# PM-1_PDB.net
KiCad netlist of a schematic drawn in Altium Designer
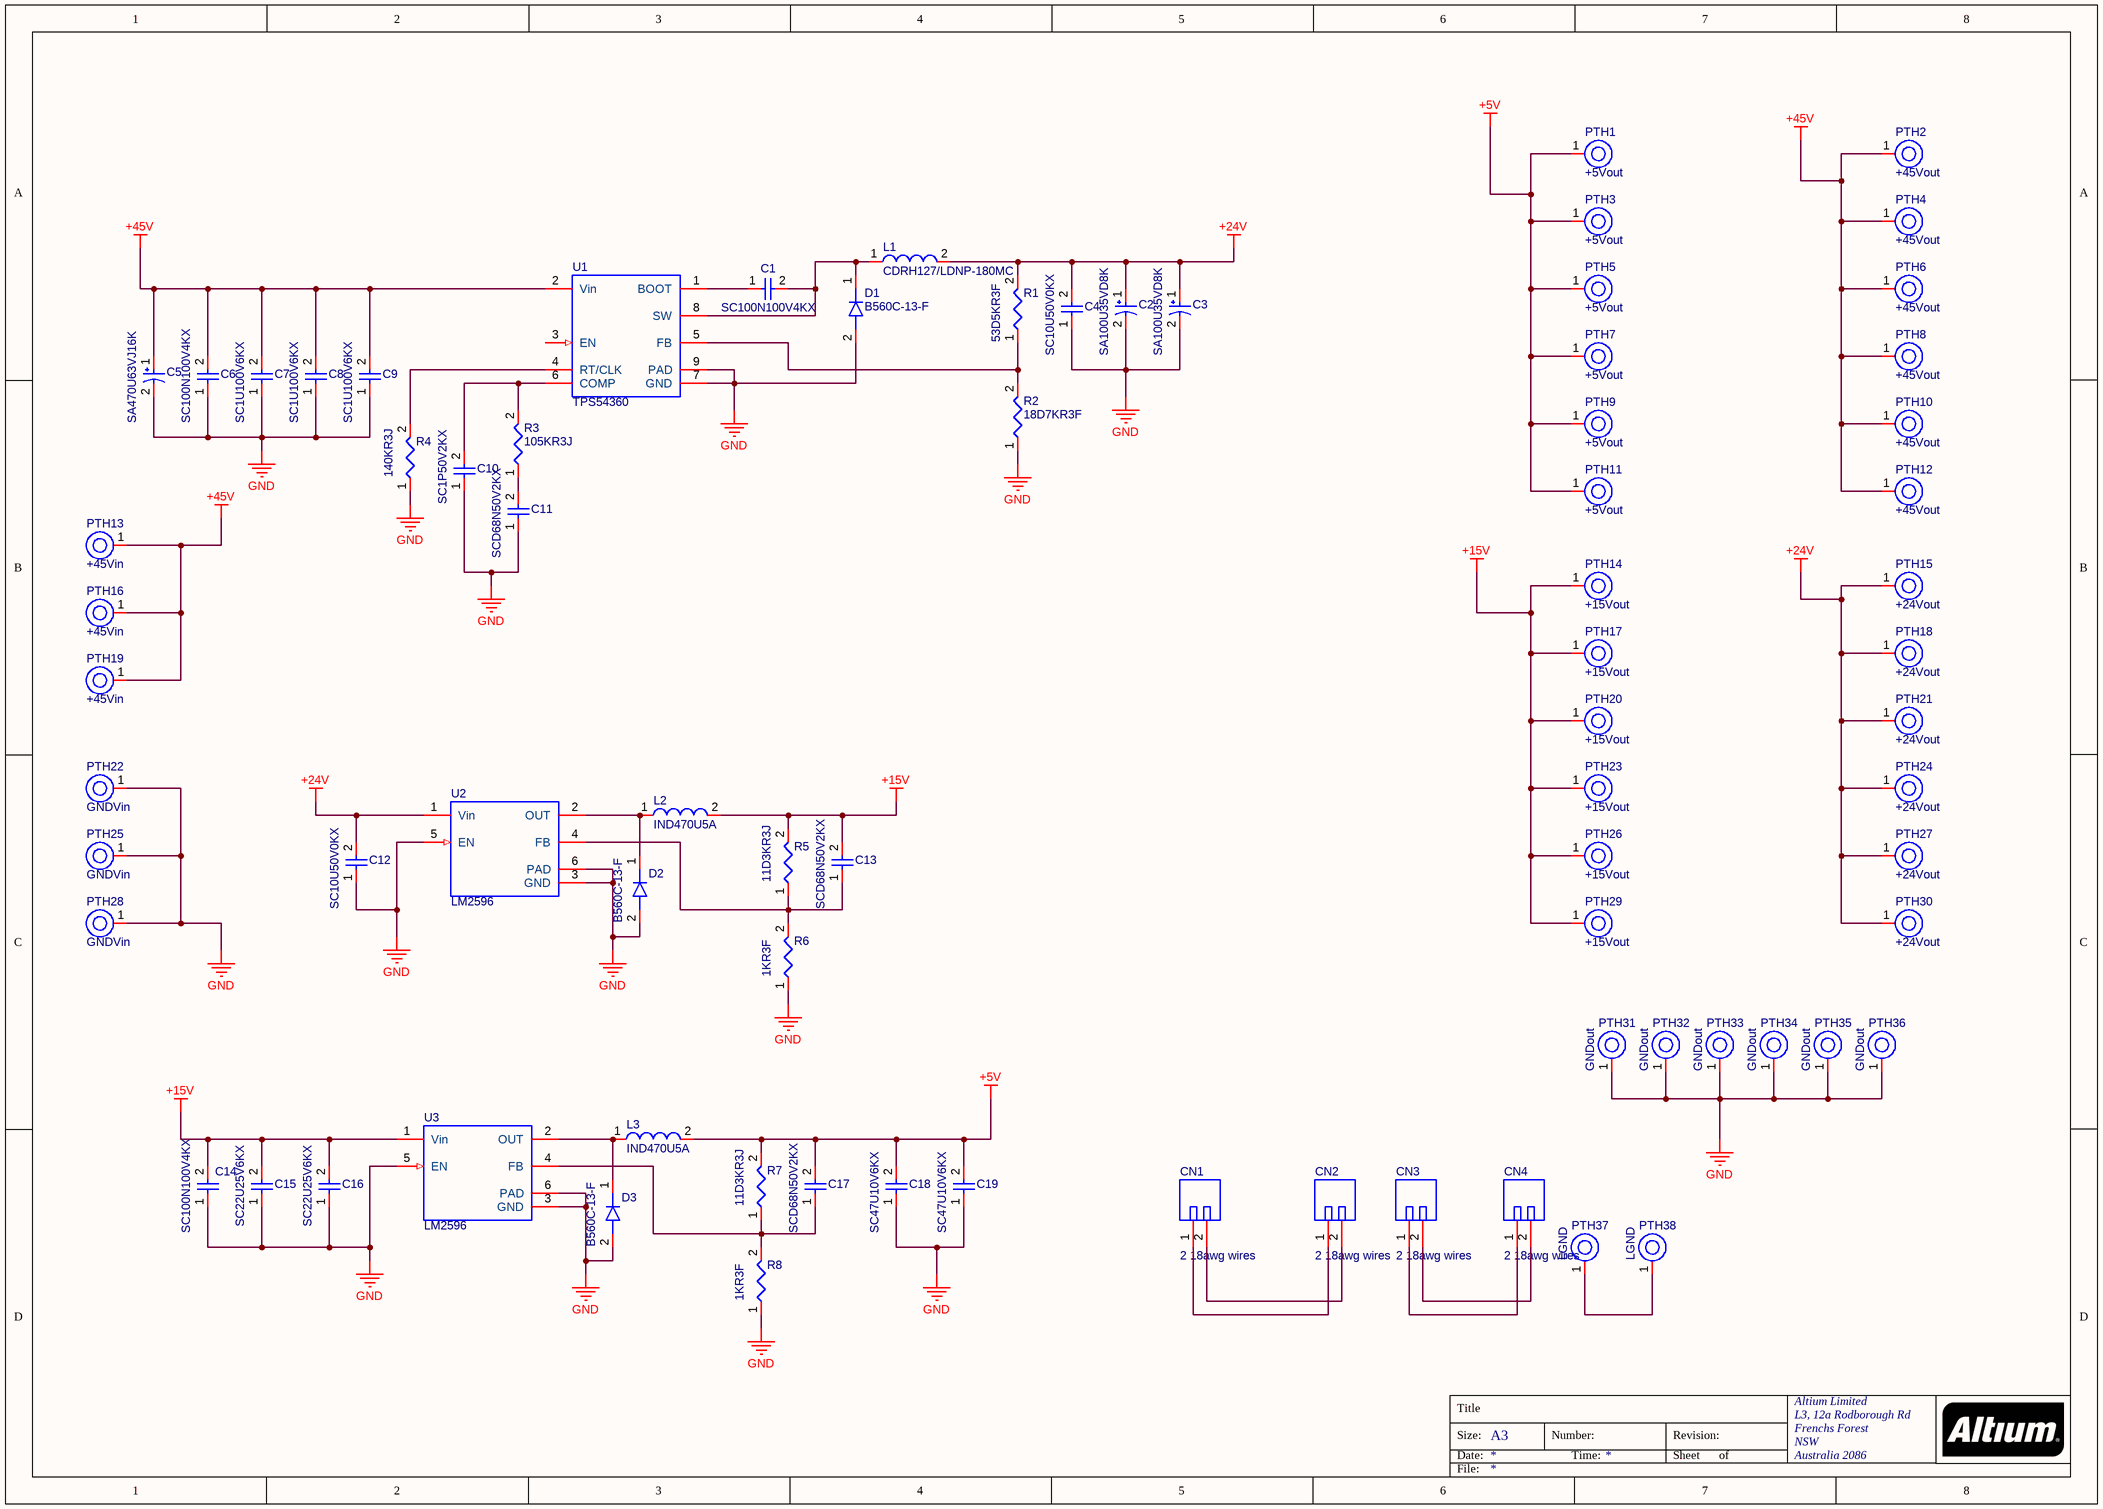
[diagram p0: PM-1_PDB.SchDoc]

(export (version "E")
  (design (tool "Eeschema 10.0.6"))
  (components
    (comp (ref "C1")
      (value "SC100N100V4KX")
      (footprint "CAPC0402(1005)60_L")
      (description "CAP 100nF 100V ±10% 0805(1610 Metric) Thickness 1mm SMD")
      (libsource (lib "PDB") (part "CAP(0805)100nF100V"))
    )
    (comp (ref "C2")
      (value "SA100U35VD8K")
      (footprint "CAPAE(D8)7666X80L")
      (description "CAP 100uF 35V ±10% D8 Thickness 7.7mm SMD")
      (libsource (lib "PDB") (part "CAP(D8)100UF35V"))
    )
    (comp (ref "C3")
      (value "SA100U35VD8K")
      (footprint "CAPAE(D8)7666X80L")
      (description "CAP 100uF 35V ±10% D8 Thickness 7.7mm SMD")
      (libsource (lib "PDB") (part "CAP(D8)100UF35V"))
    )
    (comp (ref "C4")
      (value "SC10U50V0KX")
      (footprint "CAPC3225X27L")
      (description "CAP 10uF 50V ±10% 1210(3225 Metric) Thickness 1.7mm SMD")
      (libsource (lib "PDB") (part "CAP(1210)10UF50V"))
    )
    (comp (ref "C5")
      (value "SA470U63VJ16K")
      (footprint "CAPAE184170X170L")
      (description "EEVFK1J471M CAP 470uF 63V ±10% J16 Thickness 17mm SMD")
      (libsource (lib "PDB") (part "CAP(J16)470UF63V"))
    )
    (comp (ref "C6")
      (value "SC100N100V4KX")
      (footprint "CAPC0402(1005)60_L")
      (description "CAP 100nF 100V ±10% 0805(1610 Metric) Thickness 1mm SMD")
      (libsource (lib "PDB") (part "CAP(0805)100nF100V"))
    )
    (comp (ref "C7")
      (value "SC1U100V6KX")
      (footprint "CAPC1206(3216)")
      (description "CAP 1uF 100V ±10% 1206(3216 Metric) Thickness 1.8mm SMD")
      (libsource (lib "PDB") (part "CAP(1206)1UF100V"))
    )
    (comp (ref "C8")
      (value "SC1U100V6KX")
      (footprint "CAPC1206(3216)")
      (description "CAP 1uF 100V ±10% 1206(3216 Metric) Thickness 1.8mm SMD")
      (libsource (lib "PDB") (part "CAP(1206)1UF100V"))
    )
    (comp (ref "C9")
      (value "SC1U100V6KX")
      (footprint "CAPC1206(3216)")
      (description "CAP 1uF 100V ±10% 1206(3216 Metric) Thickness 1.8mm SMD")
      (libsource (lib "PDB") (part "CAP(1206)1UF100V"))
    )
    (comp (ref "C10")
      (value "SC1P50V2KX")
      (footprint "CAPC0402(1005)60_L")
      (description "CAP 1pF 50V ±10% 0402 (1005 Metric) Thickness 0.6mm SMD")
      (libsource (lib "PDB") (part "CAP(0402)1pF50V"))
    )
    (comp (ref "C11")
      (value "SCD68N50V2KX")
      (footprint "CAPC0402(1005)60_L")
      (description "CAP 680pF 50V ±10% 0402 (1005 Metric) Thickness 0.6mm SMD")
      (libsource (lib "PDB") (part "CAP(0402)680pF50V"))
    )
    (comp (ref "C12")
      (value "SC10U50V0KX")
      (footprint "CAPC3225X27L")
      (description "CAP 10uF 50V ±10% 1210(3225 Metric) Thickness 1.7mm SMD")
      (libsource (lib "PDB") (part "CAP(1210)10UF50V"))
    )
    (comp (ref "C13")
      (value "SCD68N50V2KX")
      (footprint "CAPC0402(1005)60_L")
      (description "CAP 680pF 50V ±10% 0402 (1005 Metric) Thickness 0.6mm SMD")
      (libsource (lib "PDB") (part "CAP(0402)680pF50V"))
    )
    (comp (ref "C14")
      (value "SC100N100V4KX")
      (footprint "CAPC0402(1005)60_L")
      (description "CAP 100nF 100V ±10% 0805(1610 Metric) Thickness 1mm SMD")
      (libsource (lib "PDB") (part "CAP(0805)100nF100V"))
    )
    (comp (ref "C15")
      (value "SC22U25V6KX")
      (footprint "CAPC1206(3216)")
      (description "CAP 22uF 25V ±10% 1206(3216 Metric) Thickness 1.8mm SMD")
      (libsource (lib "PDB") (part "CAP(1206)22UF25V"))
    )
    (comp (ref "C16")
      (value "SC22U25V6KX")
      (footprint "CAPC1206(3216)")
      (description "CAP 22uF 25V ±10% 1206(3216 Metric) Thickness 1.8mm SMD")
      (libsource (lib "PDB") (part "CAP(1206)22UF25V"))
    )
    (comp (ref "C17")
      (value "SCD68N50V2KX")
      (footprint "CAPC0402(1005)60_L")
      (description "CAP 680pF 50V ±10% 0402 (1005 Metric) Thickness 0.6mm SMD")
      (libsource (lib "PDB") (part "CAP(0402)680pF50V"))
    )
    (comp (ref "C18")
      (value "SC47U10V6KX")
      (footprint "CAPC1206(3216)")
      (description "CAP 47uF 10V ±10% 1206(3216 Metric) Thickness 1.8mm SMD")
      (libsource (lib "PDB") (part "CAP(1206)47UF10V"))
    )
    (comp (ref "C19")
      (value "SC47U10V6KX")
      (footprint "CAPC1206(3216)")
      (description "CAP 47uF 10V ±10% 1206(3216 Metric) Thickness 1.8mm SMD")
      (libsource (lib "PDB") (part "CAP(1206)47UF10V"))
    )
    (comp (ref "CN1")
      (value "2 18awg wires")
      (footprint "2PHEADERS-2D54")
      (description "2 holes for 18awg wire")
      (fields (field (name "MANUFACTURER") "JST"))
      (libsource (lib "PDB") (part "2PIN-CN"))
    )
    (comp (ref "CN2")
      (value "2 18awg wires")
      (footprint "2PHEADERS-2D54")
      (description "2 holes for 18awg wire")
      (fields (field (name "MANUFACTURER") "JST"))
      (libsource (lib "PDB") (part "2PIN-CN"))
    )
    (comp (ref "CN3")
      (value "2 18awg wires")
      (footprint "2PHEADERS-2D54")
      (description "2 holes for 18awg wire")
      (fields (field (name "MANUFACTURER") "JST"))
      (libsource (lib "PDB") (part "2PIN-CN"))
    )
    (comp (ref "CN4")
      (value "2 18awg wires")
      (footprint "2PHEADERS-2D54")
      (description "2 holes for 18awg wire")
      (fields (field (name "MANUFACTURER") "JST"))
      (libsource (lib "PDB") (part "2PIN-CN"))
    )
    (comp (ref "D1")
      (value "B560C-13-F")
      (footprint "SMC")
      (description "5.0A SURFACE MOUNT SCHOTTKY BARRIER RECTIFIER")
      (fields (field (name "MANUFACTURER") "Rohm"))
      (libsource (lib "PDB") (part "DIOD-B560C"))
    )
    (comp (ref "D2")
      (value "B560C-13-F")
      (footprint "SMC")
      (description "5.0A SURFACE MOUNT SCHOTTKY BARRIER RECTIFIER")
      (fields (field (name "MANUFACTURER") "Rohm"))
      (libsource (lib "PDB") (part "DIOD-B560C"))
    )
    (comp (ref "D3")
      (value "B560C-13-F")
      (footprint "SMC")
      (description "5.0A SURFACE MOUNT SCHOTTKY BARRIER RECTIFIER")
      (fields (field (name "MANUFACTURER") "Rohm"))
      (libsource (lib "PDB") (part "DIOD-B560C"))
    )
    (comp (ref "L1")
      (value "CDRH127/LDNP-180MC")
      (footprint "INDP120120X80L")
      (description "Inductor: SMD, 18 uHn, 5.1 A")
      (libsource (lib "PDB") (part "CDRH127"))
    )
    (comp (ref "L2")
      (value "IND470U5A")
      (footprint "INDP120120X80L")
      (description "Inductor: SMD, 47 uHn, 5 A")
      (libsource (lib "PDB") (part "IND470U5A"))
    )
    (comp (ref "L3")
      (value "IND470U5A")
      (footprint "INDP120120X80L")
      (description "Inductor: SMD, 47 uHn, 5 A")
      (libsource (lib "PDB") (part "IND470U5A"))
    )
    (comp (ref "PTH1")
      (value "+5Vout")
      (footprint "POWERHOLE-LP")
      (description "1.2mm hole 2mm pad")
      (libsource (lib "PUMAlib") (part "PTH-1D2M"))
    )
    (comp (ref "PTH2")
      (value "+45Vout")
      (footprint "POWERHOLE")
      (description "2mm hole 3.5mm pad")
      (libsource (lib "PUMAlib") (part "PTH-2M"))
    )
    (comp (ref "PTH3")
      (value "+5Vout")
      (footprint "POWERHOLE-LP")
      (description "1.2mm hole 2mm pad")
      (libsource (lib "PUMAlib") (part "PTH-1D2M"))
    )
    (comp (ref "PTH4")
      (value "+45Vout")
      (footprint "POWERHOLE")
      (description "2mm hole 3.5mm pad")
      (libsource (lib "PUMAlib") (part "PTH-2M"))
    )
    (comp (ref "PTH5")
      (value "+5Vout")
      (footprint "POWERHOLE-LP")
      (description "1.2mm hole 2mm pad")
      (libsource (lib "PUMAlib") (part "PTH-1D2M"))
    )
    (comp (ref "PTH6")
      (value "+45Vout")
      (footprint "POWERHOLE")
      (description "2mm hole 3.5mm pad")
      (libsource (lib "PUMAlib") (part "PTH-2M"))
    )
    (comp (ref "PTH7")
      (value "+5Vout")
      (footprint "POWERHOLE-LP")
      (description "1.2mm hole 2mm pad")
      (libsource (lib "PUMAlib") (part "PTH-1D2M"))
    )
    (comp (ref "PTH8")
      (value "+45Vout")
      (footprint "POWERHOLE")
      (description "2mm hole 3.5mm pad")
      (libsource (lib "PUMAlib") (part "PTH-2M"))
    )
    (comp (ref "PTH9")
      (value "+5Vout")
      (footprint "POWERHOLE-LP")
      (description "1.2mm hole 2mm pad")
      (libsource (lib "PUMAlib") (part "PTH-1D2M"))
    )
    (comp (ref "PTH10")
      (value "+45Vout")
      (footprint "POWERHOLE")
      (description "2mm hole 3.5mm pad")
      (libsource (lib "PUMAlib") (part "PTH-2M"))
    )
    (comp (ref "PTH11")
      (value "+5Vout")
      (footprint "POWERHOLE-LP")
      (description "1.2mm hole 2mm pad")
      (libsource (lib "PUMAlib") (part "PTH-1D2M"))
    )
    (comp (ref "PTH12")
      (value "+45Vout")
      (footprint "POWERHOLE")
      (description "2mm hole 3.5mm pad")
      (libsource (lib "PUMAlib") (part "PTH-2M"))
    )
    (comp (ref "PTH13")
      (value "+45Vin")
      (footprint "POWERHOLE")
      (description "2mm hole 3.5mm pad")
      (libsource (lib "PUMAlib") (part "PTH-2M"))
    )
    (comp (ref "PTH14")
      (value "+15Vout")
      (footprint "POWERHOLE-LP")
      (description "1.2mm hole 2mm pad")
      (libsource (lib "PUMAlib") (part "PTH-1D2M"))
    )
    (comp (ref "PTH15")
      (value "+24Vout")
      (footprint "POWERHOLE")
      (description "2mm hole 3.5mm pad")
      (libsource (lib "PUMAlib") (part "PTH-2M"))
    )
    (comp (ref "PTH16")
      (value "+45Vin")
      (footprint "POWERHOLE")
      (description "2mm hole 3.5mm pad")
      (libsource (lib "PUMAlib") (part "PTH-2M"))
    )
    (comp (ref "PTH17")
      (value "+15Vout")
      (footprint "POWERHOLE-LP")
      (description "1.2mm hole 2mm pad")
      (libsource (lib "PUMAlib") (part "PTH-1D2M"))
    )
    (comp (ref "PTH18")
      (value "+24Vout")
      (footprint "POWERHOLE")
      (description "2mm hole 3.5mm pad")
      (libsource (lib "PUMAlib") (part "PTH-2M"))
    )
    (comp (ref "PTH19")
      (value "+45Vin")
      (footprint "POWERHOLE")
      (description "2mm hole 3.5mm pad")
      (libsource (lib "PUMAlib") (part "PTH-2M"))
    )
    (comp (ref "PTH20")
      (value "+15Vout")
      (footprint "POWERHOLE-LP")
      (description "1.2mm hole 2mm pad")
      (libsource (lib "PUMAlib") (part "PTH-1D2M"))
    )
    (comp (ref "PTH21")
      (value "+24Vout")
      (footprint "POWERHOLE")
      (description "2mm hole 3.5mm pad")
      (libsource (lib "PUMAlib") (part "PTH-2M"))
    )
    (comp (ref "PTH22")
      (value "GNDVin")
      (footprint "POWERHOLE")
      (description "2mm hole 3.5mm pad")
      (libsource (lib "PUMAlib") (part "PTH-2M"))
    )
    (comp (ref "PTH23")
      (value "+15Vout")
      (footprint "POWERHOLE-LP")
      (description "1.2mm hole 2mm pad")
      (libsource (lib "PUMAlib") (part "PTH-1D2M"))
    )
    (comp (ref "PTH24")
      (value "+24Vout")
      (footprint "POWERHOLE")
      (description "2mm hole 3.5mm pad")
      (libsource (lib "PUMAlib") (part "PTH-2M"))
    )
    (comp (ref "PTH25")
      (value "GNDVin")
      (footprint "POWERHOLE")
      (description "2mm hole 3.5mm pad")
      (libsource (lib "PUMAlib") (part "PTH-2M"))
    )
    (comp (ref "PTH26")
      (value "+15Vout")
      (footprint "POWERHOLE-LP")
      (description "1.2mm hole 2mm pad")
      (libsource (lib "PUMAlib") (part "PTH-1D2M"))
    )
    (comp (ref "PTH27")
      (value "+24Vout")
      (footprint "POWERHOLE")
      (description "2mm hole 3.5mm pad")
      (libsource (lib "PUMAlib") (part "PTH-2M"))
    )
    (comp (ref "PTH28")
      (value "GNDVin")
      (footprint "POWERHOLE")
      (description "2mm hole 3.5mm pad")
      (libsource (lib "PUMAlib") (part "PTH-2M"))
    )
    (comp (ref "PTH29")
      (value "+15Vout")
      (footprint "POWERHOLE-LP")
      (description "1.2mm hole 2mm pad")
      (libsource (lib "PUMAlib") (part "PTH-1D2M"))
    )
    (comp (ref "PTH30")
      (value "+24Vout")
      (footprint "POWERHOLE")
      (description "2mm hole 3.5mm pad")
      (libsource (lib "PUMAlib") (part "PTH-2M"))
    )
    (comp (ref "PTH31")
      (value "GNDout")
      (footprint "POWERHOLE")
      (description "2mm hole 3.5mm pad")
      (libsource (lib "PUMAlib") (part "PTH-2M"))
    )
    (comp (ref "PTH32")
      (value "GNDout")
      (footprint "POWERHOLE")
      (description "2mm hole 3.5mm pad")
      (libsource (lib "PUMAlib") (part "PTH-2M"))
    )
    (comp (ref "PTH33")
      (value "GNDout")
      (footprint "POWERHOLE")
      (description "2mm hole 3.5mm pad")
      (libsource (lib "PUMAlib") (part "PTH-2M"))
    )
    (comp (ref "PTH34")
      (value "GNDout")
      (footprint "POWERHOLE")
      (description "2mm hole 3.5mm pad")
      (libsource (lib "PUMAlib") (part "PTH-2M"))
    )
    (comp (ref "PTH35")
      (value "GNDout")
      (footprint "POWERHOLE")
      (description "2mm hole 3.5mm pad")
      (libsource (lib "PUMAlib") (part "PTH-2M"))
    )
    (comp (ref "PTH36")
      (value "GNDout")
      (footprint "POWERHOLE")
      (description "2mm hole 3.5mm pad")
      (libsource (lib "PUMAlib") (part "PTH-2M"))
    )
    (comp (ref "PTH37")
      (value "LGND")
      (footprint "POWERHOLE-LP")
      (description "1.2mm hole 2mm pad")
      (libsource (lib "PUMAlib") (part "PTH-1D2M"))
    )
    (comp (ref "PTH38")
      (value "LGND")
      (footprint "POWERHOLE-LP")
      (description "1.2mm hole 2mm pad")
      (libsource (lib "PUMAlib") (part "PTH-1D2M"))
    )
    (comp (ref "R1")
      (value "53D5KR3F")
      (footprint "RESC0603(1608)_L")
      (description "53.5K 0.1W 1% 0603 (1608 Metric)  SMD")
      (libsource (lib "PDB") (part "RES0(0603)_53D5K"))
    )
    (comp (ref "R2")
      (value "18D7KR3F")
      (footprint "RESC0603(1608)_L")
      (description "18.7K 0.1W 1% 0603 (1608 Metric)  SMD")
      (libsource (lib "PDB") (part "RES0(0603)_1D8K"))
    )
    (comp (ref "R3")
      (value "105KR3J")
      (footprint "RESC0603(1608)_L")
      (description "105K 0.1W 5% 0603 (1608 Metric)  SMD")
      (libsource (lib "PDB") (part "RES0(0603)_105K"))
    )
    (comp (ref "R4")
      (value "140KR3J")
      (footprint "RESC0603(1608)_L")
      (description "140K 0.1W 5% 0603 (1608 Metric)  SMD")
      (libsource (lib "PDB") (part "RES0(0603)_140K"))
    )
    (comp (ref "R5")
      (value "11D3KR3J")
      (footprint "RESC0603(1608)_L")
      (description "11.3K 0.1W 5% 0603 (1608 Metric)  SMD")
      (libsource (lib "PDB") (part "RES0(0603)_11D3K"))
    )
    (comp (ref "R6")
      (value "1KR3F")
      (footprint "RESC0603(1608)_L")
      (description "1K 0.1W 1% 0603 (1608 Metric)  SMD")
      (libsource (lib "PDB") (part "RES0(0603)_1K"))
    )
    (comp (ref "R7")
      (value "11D3KR3J")
      (footprint "RESC0603(1608)_L")
      (description "11.3K 0.1W 5% 0603 (1608 Metric)  SMD")
      (libsource (lib "PDB") (part "RES0(0603)_11D3K"))
    )
    (comp (ref "R8")
      (value "1KR3F")
      (footprint "RESC0603(1608)_L")
      (description "1K 0.1W 1% 0603 (1608 Metric)  SMD")
      (libsource (lib "PDB") (part "RES0(0603)_1K"))
    )
    (comp (ref "U1")
      (value "TPS54360")
      (footprint "POWERSO8")
      (description "60 V Input, 3.5 A, Step Down DC-DC Converter")
      (libsource (lib "PDB") (part "TPS54360"))
    )
    (comp (ref "U2")
      (value "LM2596")
      (footprint "D2PAK")
      (description "4 V Input, 3 A, Step Down DC-DC Converter")
      (libsource (lib "PDB") (part "LM2596"))
    )
    (comp (ref "U3")
      (value "LM2596")
      (footprint "D2PAK")
      (description "4 V Input, 3 A, Step Down DC-DC Converter")
      (libsource (lib "PDB") (part "LM2596"))
    )
  )
  (nets
    (net (code "1") (name "+5V") (class "Default")
      (node (ref "C17") (pin "2") (pinfunction "2_2") (pintype "passive"))
      (node (ref "C18") (pin "2") (pinfunction "2_2") (pintype "passive"))
      (node (ref "C19") (pin "2") (pinfunction "2_2") (pintype "passive"))
      (node (ref "L3") (pin "2") (pinfunction "2_2") (pintype "passive"))
      (node (ref "PTH1") (pin "1") (pinfunction "H1_1") (pintype "passive"))
      (node (ref "PTH11") (pin "1") (pinfunction "H1_1") (pintype "passive"))
      (node (ref "PTH3") (pin "1") (pinfunction "H1_1") (pintype "passive"))
      (node (ref "PTH5") (pin "1") (pinfunction "H1_1") (pintype "passive"))
      (node (ref "PTH7") (pin "1") (pinfunction "H1_1") (pintype "passive"))
      (node (ref "PTH9") (pin "1") (pinfunction "H1_1") (pintype "passive"))
      (node (ref "R7") (pin "2") (pinfunction "2_2") (pintype "passive"))
    )
    (net (code "2") (name "+15V") (class "Default")
      (node (ref "C13") (pin "2") (pinfunction "2_2") (pintype "passive"))
      (node (ref "C14") (pin "2") (pinfunction "2_2") (pintype "passive"))
      (node (ref "C15") (pin "2") (pinfunction "2_2") (pintype "passive"))
      (node (ref "C16") (pin "2") (pinfunction "2_2") (pintype "passive"))
      (node (ref "L2") (pin "2") (pinfunction "2_2") (pintype "passive"))
      (node (ref "PTH14") (pin "1") (pinfunction "H1_1") (pintype "passive"))
      (node (ref "PTH17") (pin "1") (pinfunction "H1_1") (pintype "passive"))
      (node (ref "PTH20") (pin "1") (pinfunction "H1_1") (pintype "passive"))
      (node (ref "PTH23") (pin "1") (pinfunction "H1_1") (pintype "passive"))
      (node (ref "PTH26") (pin "1") (pinfunction "H1_1") (pintype "passive"))
      (node (ref "PTH29") (pin "1") (pinfunction "H1_1") (pintype "passive"))
      (node (ref "R5") (pin "2") (pinfunction "2_2") (pintype "passive"))
      (node (ref "U3") (pin "1") (pinfunction "Vin_1") (pintype "power_in"))
    )
    (net (code "3") (name "+24V") (class "Default")
      (node (ref "C12") (pin "2") (pinfunction "2_2") (pintype "passive"))
      (node (ref "C2") (pin "1") (pinfunction "1_1") (pintype "passive"))
      (node (ref "C3") (pin "1") (pinfunction "1_1") (pintype "passive"))
      (node (ref "C4") (pin "2") (pinfunction "2_2") (pintype "passive"))
      (node (ref "L1") (pin "2") (pinfunction "2_2") (pintype "passive"))
      (node (ref "PTH15") (pin "1") (pinfunction "H1_1") (pintype "passive"))
      (node (ref "PTH18") (pin "1") (pinfunction "H1_1") (pintype "passive"))
      (node (ref "PTH21") (pin "1") (pinfunction "H1_1") (pintype "passive"))
      (node (ref "PTH24") (pin "1") (pinfunction "H1_1") (pintype "passive"))
      (node (ref "PTH27") (pin "1") (pinfunction "H1_1") (pintype "passive"))
      (node (ref "PTH30") (pin "1") (pinfunction "H1_1") (pintype "passive"))
      (node (ref "R1") (pin "2") (pinfunction "2_2") (pintype "passive"))
      (node (ref "U2") (pin "1") (pinfunction "Vin_1") (pintype "power_in"))
    )
    (net (code "4") (name "+45V") (class "Default")
      (node (ref "C5") (pin "1") (pinfunction "1_1") (pintype "passive"))
      (node (ref "C6") (pin "2") (pinfunction "2_2") (pintype "passive"))
      (node (ref "C7") (pin "2") (pinfunction "2_2") (pintype "passive"))
      (node (ref "C8") (pin "2") (pinfunction "2_2") (pintype "passive"))
      (node (ref "C9") (pin "2") (pinfunction "2_2") (pintype "passive"))
      (node (ref "PTH10") (pin "1") (pinfunction "H1_1") (pintype "passive"))
      (node (ref "PTH12") (pin "1") (pinfunction "H1_1") (pintype "passive"))
      (node (ref "PTH13") (pin "1") (pinfunction "H1_1") (pintype "passive"))
      (node (ref "PTH16") (pin "1") (pinfunction "H1_1") (pintype "passive"))
      (node (ref "PTH19") (pin "1") (pinfunction "H1_1") (pintype "passive"))
      (node (ref "PTH2") (pin "1") (pinfunction "H1_1") (pintype "passive"))
      (node (ref "PTH4") (pin "1") (pinfunction "H1_1") (pintype "passive"))
      (node (ref "PTH6") (pin "1") (pinfunction "H1_1") (pintype "passive"))
      (node (ref "PTH8") (pin "1") (pinfunction "H1_1") (pintype "passive"))
      (node (ref "U1") (pin "2") (pinfunction "Vin_2") (pintype "power_in"))
    )
    (net (code "5") (name "GND") (class "Default")
      (node (ref "C10") (pin "1") (pinfunction "1_1") (pintype "passive"))
      (node (ref "C11") (pin "1") (pinfunction "1_1") (pintype "passive"))
      (node (ref "C12") (pin "1") (pinfunction "1_1") (pintype "passive"))
      (node (ref "C14") (pin "1") (pinfunction "1_1") (pintype "passive"))
      (node (ref "C15") (pin "1") (pinfunction "1_1") (pintype "passive"))
      (node (ref "C16") (pin "1") (pinfunction "1_1") (pintype "passive"))
      (node (ref "C18") (pin "1") (pinfunction "1_1") (pintype "passive"))
      (node (ref "C19") (pin "1") (pinfunction "1_1") (pintype "passive"))
      (node (ref "C2") (pin "2") (pinfunction "2_2") (pintype "passive"))
      (node (ref "C3") (pin "2") (pinfunction "2_2") (pintype "passive"))
      (node (ref "C4") (pin "1") (pinfunction "1_1") (pintype "passive"))
      (node (ref "C5") (pin "2") (pinfunction "2_2") (pintype "passive"))
      (node (ref "C6") (pin "1") (pinfunction "1_1") (pintype "passive"))
      (node (ref "C7") (pin "1") (pinfunction "1_1") (pintype "passive"))
      (node (ref "C8") (pin "1") (pinfunction "1_1") (pintype "passive"))
      (node (ref "C9") (pin "1") (pinfunction "1_1") (pintype "passive"))
      (node (ref "D1") (pin "2") (pinfunction "A_2") (pintype "passive"))
      (node (ref "D2") (pin "2") (pinfunction "A_2") (pintype "passive"))
      (node (ref "D3") (pin "2") (pinfunction "A_2") (pintype "passive"))
      (node (ref "PTH22") (pin "1") (pinfunction "H1_1") (pintype "passive"))
      (node (ref "PTH25") (pin "1") (pinfunction "H1_1") (pintype "passive"))
      (node (ref "PTH28") (pin "1") (pinfunction "H1_1") (pintype "passive"))
      (node (ref "PTH31") (pin "1") (pinfunction "H1_1") (pintype "passive"))
      (node (ref "PTH32") (pin "1") (pinfunction "H1_1") (pintype "passive"))
      (node (ref "PTH33") (pin "1") (pinfunction "H1_1") (pintype "passive"))
      (node (ref "PTH34") (pin "1") (pinfunction "H1_1") (pintype "passive"))
      (node (ref "PTH35") (pin "1") (pinfunction "H1_1") (pintype "passive"))
      (node (ref "PTH36") (pin "1") (pinfunction "H1_1") (pintype "passive"))
      (node (ref "R2") (pin "1") (pinfunction "1_1") (pintype "passive"))
      (node (ref "R4") (pin "1") (pinfunction "1_1") (pintype "passive"))
      (node (ref "R6") (pin "1") (pinfunction "1_1") (pintype "passive"))
      (node (ref "R8") (pin "1") (pinfunction "1_1") (pintype "passive"))
      (node (ref "U1") (pin "7") (pinfunction "GND_7") (pintype "power_in"))
      (node (ref "U1") (pin "9") (pinfunction "PAD_9") (pintype "passive"))
      (node (ref "U2") (pin "3") (pinfunction "GND_3") (pintype "power_in"))
      (node (ref "U2") (pin "5") (pinfunction "EN_5") (pintype "input"))
      (node (ref "U2") (pin "6") (pinfunction "PAD_6") (pintype "passive"))
      (node (ref "U3") (pin "3") (pinfunction "GND_3") (pintype "power_in"))
      (node (ref "U3") (pin "5") (pinfunction "EN_5") (pintype "input"))
      (node (ref "U3") (pin "6") (pinfunction "PAD_6") (pintype "passive"))
    )
    (net (code "6") (name "Net-(C11-Pad2)") (class "Default")
      (node (ref "C11") (pin "2") (pinfunction "2_2") (pintype "passive"))
      (node (ref "R3") (pin "1") (pinfunction "1_1") (pintype "passive"))
    )
    (net (code "7") (name "Net-(CN1-Pad1)") (class "Default")
      (node (ref "CN1") (pin "1") (pinfunction "1_1") (pintype "passive"))
      (node (ref "CN2") (pin "1") (pinfunction "1_1") (pintype "passive"))
    )
    (net (code "8") (name "Net-(CN1-Pad2)") (class "Default")
      (node (ref "CN1") (pin "2") (pinfunction "2_2") (pintype "passive"))
      (node (ref "CN2") (pin "2") (pinfunction "2_2") (pintype "passive"))
    )
    (net (code "9") (name "Net-(CN3-Pad1)") (class "Default")
      (node (ref "CN3") (pin "1") (pinfunction "1_1") (pintype "passive"))
      (node (ref "CN4") (pin "1") (pinfunction "1_1") (pintype "passive"))
    )
    (net (code "10") (name "Net-(CN3-Pad2)") (class "Default")
      (node (ref "CN3") (pin "2") (pinfunction "2_2") (pintype "passive"))
      (node (ref "CN4") (pin "2") (pinfunction "2_2") (pintype "passive"))
    )
    (net (code "11") (name "Net-(D1-K)") (class "Default")
      (node (ref "C1") (pin "2") (pinfunction "2_2") (pintype "passive"))
      (node (ref "D1") (pin "1") (pinfunction "K_1") (pintype "passive"))
      (node (ref "L1") (pin "1") (pinfunction "1_1") (pintype "passive"))
      (node (ref "U1") (pin "8") (pinfunction "SW_8") (pintype "passive"))
    )
    (net (code "12") (name "Net-(D2-K)") (class "Default")
      (node (ref "D2") (pin "1") (pinfunction "K_1") (pintype "passive"))
      (node (ref "L2") (pin "1") (pinfunction "1_1") (pintype "passive"))
      (node (ref "U2") (pin "2") (pinfunction "OUT_2") (pintype "passive"))
    )
    (net (code "13") (name "Net-(D3-K)") (class "Default")
      (node (ref "D3") (pin "1") (pinfunction "K_1") (pintype "passive"))
      (node (ref "L3") (pin "1") (pinfunction "1_1") (pintype "passive"))
      (node (ref "U3") (pin "2") (pinfunction "OUT_2") (pintype "passive"))
    )
    (net (code "14") (name "Net-(PTH37-H1)") (class "Default")
      (node (ref "PTH37") (pin "1") (pinfunction "H1_1") (pintype "passive"))
      (node (ref "PTH38") (pin "1") (pinfunction "H1_1") (pintype "passive"))
    )
    (net (code "15") (name "Net-(U1-BOOT)") (class "Default")
      (node (ref "C1") (pin "1") (pinfunction "1_1") (pintype "passive"))
      (node (ref "U1") (pin "1") (pinfunction "BOOT_1") (pintype "passive"))
    )
    (net (code "16") (name "Net-(U1-COMP)") (class "Default")
      (node (ref "C10") (pin "2") (pinfunction "2_2") (pintype "passive"))
      (node (ref "R3") (pin "2") (pinfunction "2_2") (pintype "passive"))
      (node (ref "U1") (pin "6") (pinfunction "COMP_6") (pintype "passive"))
    )
    (net (code "17") (name "Net-(U1-FB)") (class "Default")
      (node (ref "R1") (pin "1") (pinfunction "1_1") (pintype "passive"))
      (node (ref "R2") (pin "2") (pinfunction "2_2") (pintype "passive"))
      (node (ref "U1") (pin "5") (pinfunction "FB_5") (pintype "passive"))
    )
    (net (code "18") (name "Net-(U1-RT{slash}CLK)") (class "Default")
      (node (ref "R4") (pin "2") (pinfunction "2_2") (pintype "passive"))
      (node (ref "U1") (pin "4") (pinfunction "RT/CLK_4") (pintype "passive"))
    )
    (net (code "19") (name "Net-(U2-FB)") (class "Default")
      (node (ref "C13") (pin "1") (pinfunction "1_1") (pintype "passive"))
      (node (ref "R5") (pin "1") (pinfunction "1_1") (pintype "passive"))
      (node (ref "R6") (pin "2") (pinfunction "2_2") (pintype "passive"))
      (node (ref "U2") (pin "4") (pinfunction "FB_4") (pintype "passive"))
    )
    (net (code "20") (name "Net-(U3-FB)") (class "Default")
      (node (ref "C17") (pin "1") (pinfunction "1_1") (pintype "passive"))
      (node (ref "R7") (pin "1") (pinfunction "1_1") (pintype "passive"))
      (node (ref "R8") (pin "2") (pinfunction "2_2") (pintype "passive"))
      (node (ref "U3") (pin "4") (pinfunction "FB_4") (pintype "passive"))
    )
    (net (code "21") (name "unconnected-(U1-EN-Pad3)") (class "Default")
      (node (ref "U1") (pin "3") (pinfunction "EN_3") (pintype "input"))
    )
  )
)
